# i2c_rs232_interface.net
KiCad netlist of a schematic drawn in EAGLE
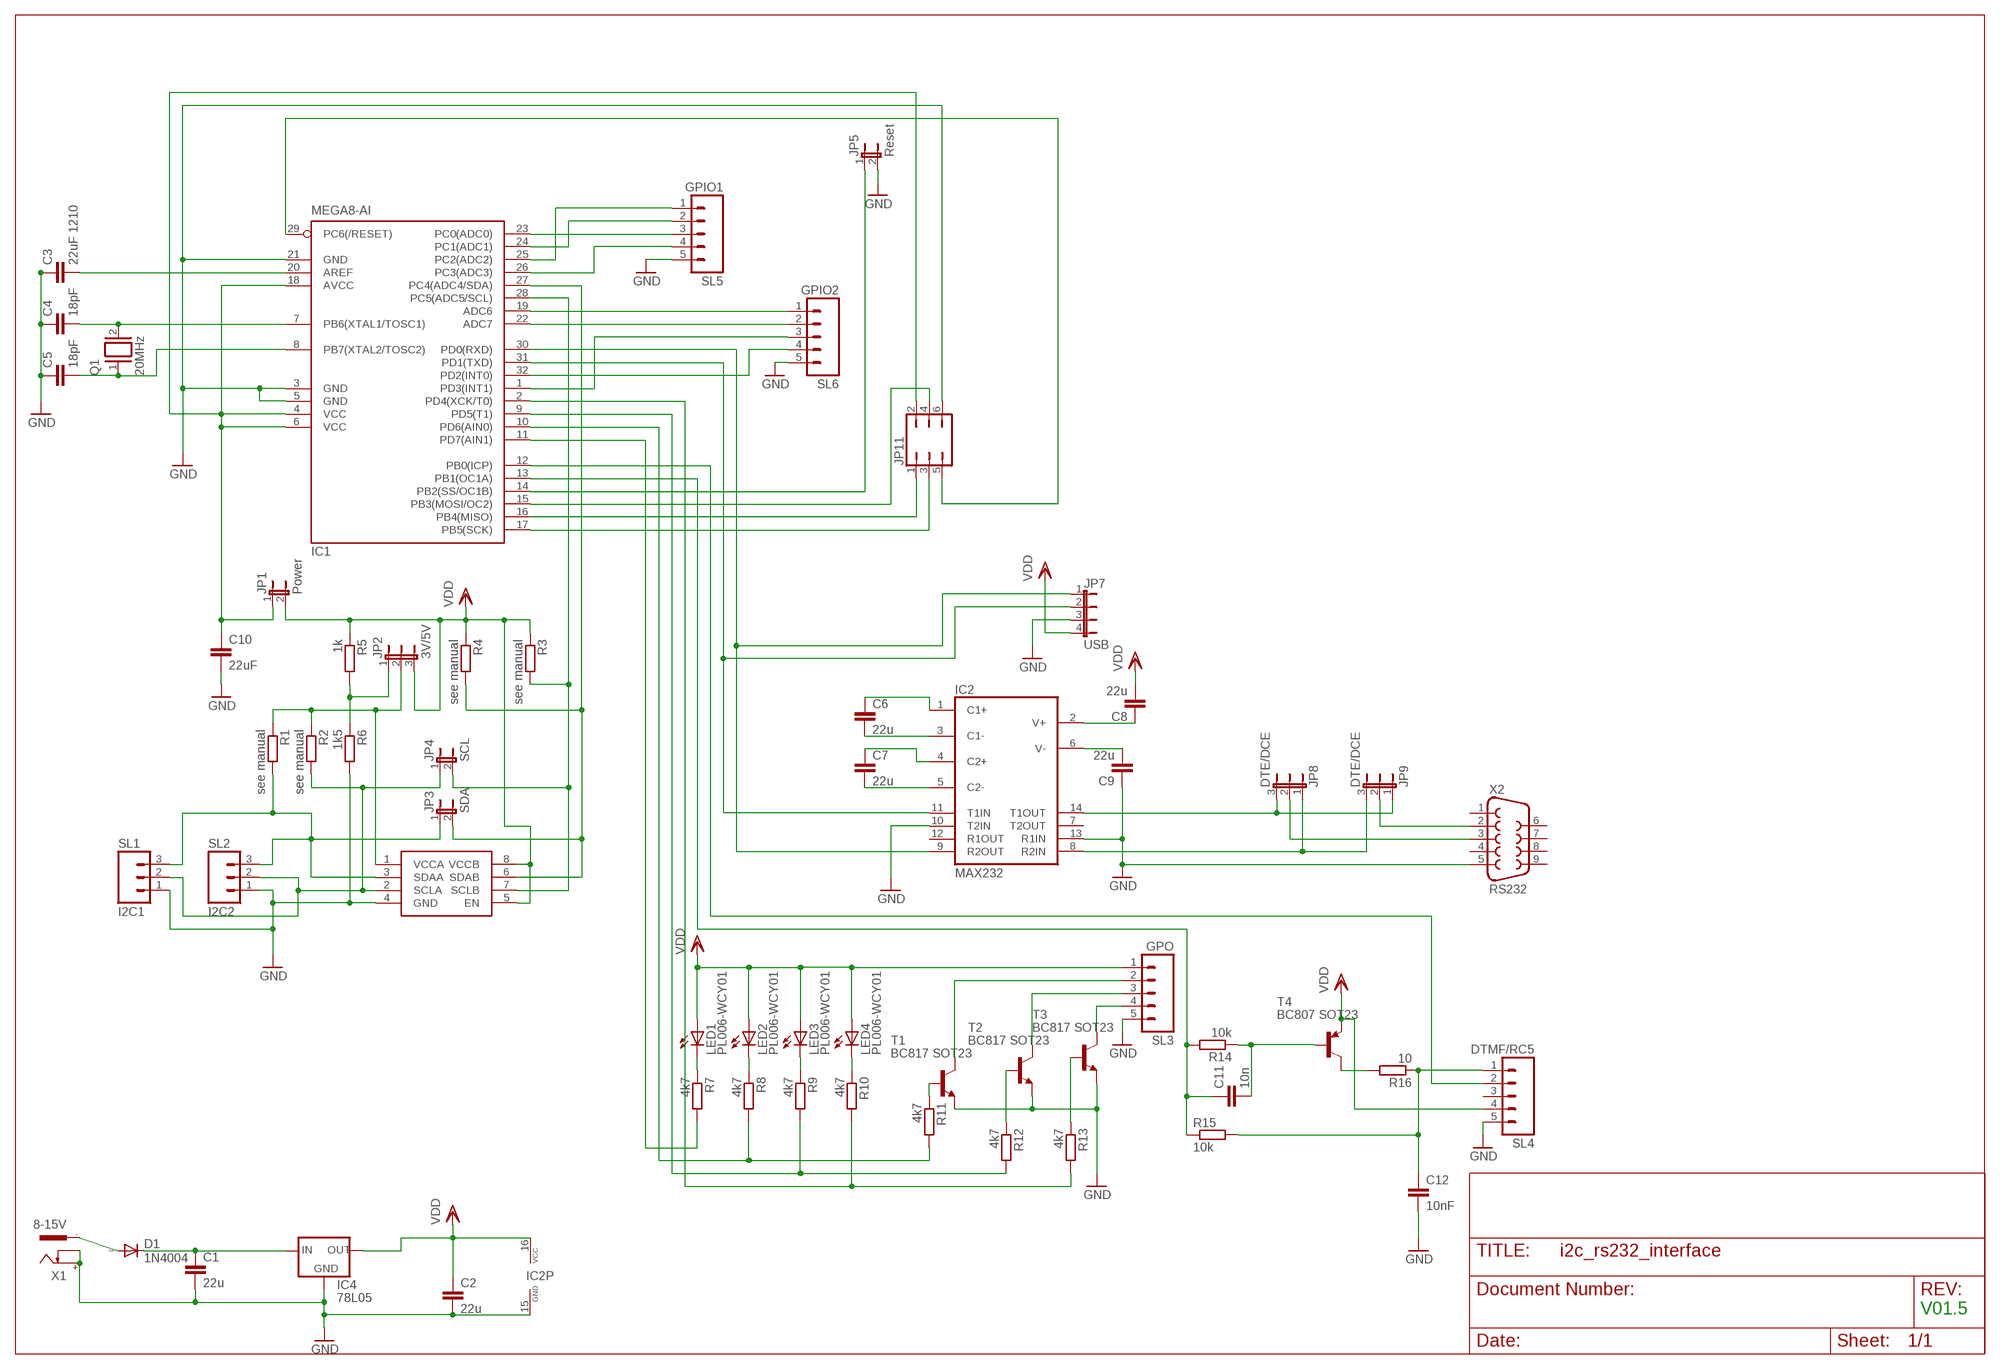
[diagram p0: schematic, sheet 1]

(export (version "E")
  (design (tool "Eeschema 10.0.6"))
  (components
    (comp (ref "C1")
      (value "22u")
      (footprint "eagle-import:C1206")
      (libsource (lib "eagle-import") (part "C-EUC1206"))
    )
    (comp (ref "C2")
      (value "22u")
      (footprint "eagle-import:C1206")
      (libsource (lib "eagle-import") (part "C-EUC1206"))
    )
    (comp (ref "C3")
      (value "22uF 1210")
      (footprint "eagle-import:C1206")
      (libsource (lib "eagle-import") (part "C-EUC1206"))
    )
    (comp (ref "C4")
      (value "18pF")
      (footprint "eagle-import:C025-025X050")
      (libsource (lib "eagle-import") (part "resistor_C-EU025-025X050"))
    )
    (comp (ref "C5")
      (value "18pF")
      (footprint "eagle-import:C025-025X050")
      (libsource (lib "eagle-import") (part "resistor_C-EU025-025X050"))
    )
    (comp (ref "C6")
      (value "22u")
      (footprint "eagle-import:C1206")
      (libsource (lib "eagle-import") (part "C-EUC1206"))
    )
    (comp (ref "C7")
      (value "22u")
      (footprint "eagle-import:C1206")
      (libsource (lib "eagle-import") (part "C-EUC1206"))
    )
    (comp (ref "C8")
      (value "22u")
      (footprint "eagle-import:C1206")
      (libsource (lib "eagle-import") (part "C-EUC1206"))
    )
    (comp (ref "C9")
      (value "22u")
      (footprint "eagle-import:C1206")
      (libsource (lib "eagle-import") (part "C-EUC1206"))
    )
    (comp (ref "C10")
      (value "22uF")
      (footprint "eagle-import:C1206")
      (libsource (lib "eagle-import") (part "C-EUC1206"))
    )
    (comp (ref "C11")
      (value "10n")
      (footprint "eagle-import:C1206")
      (libsource (lib "eagle-import") (part "resistor_C-EUC1206"))
    )
    (comp (ref "C12")
      (value "10nF")
      (footprint "eagle-import:C1206")
      (libsource (lib "eagle-import") (part "resistor_C-EUC1206"))
    )
    (comp (ref "D1")
      (value "1N4004")
      (footprint "eagle-import:DO41-10")
      (libsource (lib "eagle-import") (part "1N4004"))
    )
    (comp (ref "IC1")
      (value "MEGA8-AI")
      (footprint "eagle-import:TQFP32-08")
      (fields (field (name "MPN") "ATMEGA8-16AU"))
      (libsource (lib "eagle-import") (part "MEGA8-AI"))
    )
    (comp (ref "IC2")
      (value "MAX232")
      (footprint "eagle-import:DIL16")
      (fields (field (name "MF") "MAXIM") (field (name "MPN") "MAX232ACPE+"))
      (libsource (lib "eagle-import") (part "MAX232"))
    )
    (comp (ref "IC3")
      (value "PCA9517")
      (footprint "eagle-import:SO-08")
      (libsource (lib "eagle-import") (part "PCA9517"))
    )
    (comp (ref "IC4")
      (value "78L05")
      (footprint "eagle-import:78LXX")
      (libsource (lib "eagle-import") (part "78LXX"))
    )
    (comp (ref "JP1")
      (value "Power")
      (footprint "eagle-import:JP1")
      (libsource (lib "eagle-import") (part "JP1E"))
    )
    (comp (ref "JP2")
      (value "3V/5V")
      (footprint "eagle-import:JP2")
      (libsource (lib "eagle-import") (part "JP2E"))
    )
    (comp (ref "JP3")
      (value "SDA")
      (footprint "eagle-import:JP1")
      (libsource (lib "eagle-import") (part "JP1E"))
    )
    (comp (ref "JP4")
      (value "SCL")
      (footprint "eagle-import:JP1")
      (libsource (lib "eagle-import") (part "JP1E"))
    )
    (comp (ref "JP5")
      (value "Reset")
      (footprint "eagle-import:JP1")
      (libsource (lib "eagle-import") (part "JP1E"))
    )
    (comp (ref "JP7")
      (value "USB")
      (footprint "eagle-import:JP4")
      (libsource (lib "eagle-import") (part "JP4E"))
    )
    (comp (ref "JP8")
      (value "DTE/DCE")
      (footprint "eagle-import:JP2")
      (libsource (lib "eagle-import") (part "JP2E"))
    )
    (comp (ref "JP9")
      (value "DTE/DCE")
      (footprint "eagle-import:JP2")
      (libsource (lib "eagle-import") (part "JP2E"))
    )
    (comp (ref "JP11")
      (value "JP3Q")
      (footprint "eagle-import:JP3Q")
      (libsource (lib "eagle-import") (part "JP3Q"))
    )
    (comp (ref "LED1")
      (value "PL006-WCY01")
      (footprint "eagle-import:SOT23")
      (libsource (lib "eagle-import") (part "PL006-WCY01"))
    )
    (comp (ref "LED2")
      (value "PL006-WCY01")
      (footprint "eagle-import:SOT23")
      (libsource (lib "eagle-import") (part "PL006-WCY01"))
    )
    (comp (ref "LED3")
      (value "PL006-WCY01")
      (footprint "eagle-import:SOT23")
      (libsource (lib "eagle-import") (part "PL006-WCY01"))
    )
    (comp (ref "LED4")
      (value "PL006-WCY01")
      (footprint "eagle-import:SOT23")
      (libsource (lib "eagle-import") (part "PL006-WCY01"))
    )
    (comp (ref "Q1")
      (value "20MHz")
      (footprint "eagle-import:QS")
      (libsource (lib "eagle-import") (part "XTAL/S"))
    )
    (comp (ref "R1")
      (value "see manual")
      (footprint "eagle-import:R1206")
      (libsource (lib "eagle-import") (part "R-EU_R1206"))
    )
    (comp (ref "R2")
      (value "see manual")
      (footprint "eagle-import:R1206")
      (libsource (lib "eagle-import") (part "R-EU_R1206"))
    )
    (comp (ref "R3")
      (value "see manual")
      (footprint "eagle-import:R1206")
      (libsource (lib "eagle-import") (part "R-EU_R1206"))
    )
    (comp (ref "R4")
      (value "see manual")
      (footprint "eagle-import:R1206")
      (libsource (lib "eagle-import") (part "R-EU_R1206"))
    )
    (comp (ref "R5")
      (value "1k")
      (footprint "eagle-import:R1206")
      (libsource (lib "eagle-import") (part "R-EU_R1206"))
    )
    (comp (ref "R6")
      (value "1k5")
      (footprint "eagle-import:R1206")
      (libsource (lib "eagle-import") (part "R-EU_R1206"))
    )
    (comp (ref "R7")
      (value "4k7")
      (footprint "eagle-import:R1206")
      (libsource (lib "eagle-import") (part "R-EU_R1206"))
    )
    (comp (ref "R8")
      (value "4k7")
      (footprint "eagle-import:R1206")
      (libsource (lib "eagle-import") (part "R-EU_R1206"))
    )
    (comp (ref "R9")
      (value "4k7")
      (footprint "eagle-import:R1206")
      (libsource (lib "eagle-import") (part "R-EU_R1206"))
    )
    (comp (ref "R10")
      (value "4k7")
      (footprint "eagle-import:R1206")
      (libsource (lib "eagle-import") (part "R-EU_R1206"))
    )
    (comp (ref "R11")
      (value "4k7")
      (footprint "eagle-import:R1206")
      (libsource (lib "eagle-import") (part "R-EU_R1206"))
    )
    (comp (ref "R12")
      (value "4k7")
      (footprint "eagle-import:R1206")
      (libsource (lib "eagle-import") (part "R-EU_R1206"))
    )
    (comp (ref "R13")
      (value "4k7")
      (footprint "eagle-import:R1206")
      (libsource (lib "eagle-import") (part "R-EU_R1206"))
    )
    (comp (ref "R14")
      (value "10k")
      (footprint "eagle-import:R1206")
      (libsource (lib "eagle-import") (part "R-EU_R1206"))
    )
    (comp (ref "R15")
      (value "10k")
      (footprint "eagle-import:R1206")
      (libsource (lib "eagle-import") (part "R-EU_R1206"))
    )
    (comp (ref "R16")
      (value "10")
      (footprint "eagle-import:R1206")
      (libsource (lib "eagle-import") (part "R-EU_R1206"))
    )
    (comp (ref "SL1")
      (value "I2C1")
      (footprint "eagle-import:03P")
      (libsource (lib "eagle-import") (part "M03"))
    )
    (comp (ref "SL2")
      (value "I2C2")
      (footprint "eagle-import:03P")
      (libsource (lib "eagle-import") (part "M03"))
    )
    (comp (ref "SL3")
      (value "GPO")
      (footprint "eagle-import:05P")
      (libsource (lib "eagle-import") (part "M05"))
    )
    (comp (ref "SL4")
      (value "DTMF/RC5")
      (footprint "eagle-import:05P")
      (libsource (lib "eagle-import") (part "M05"))
    )
    (comp (ref "SL5")
      (value "GPIO1")
      (footprint "eagle-import:05P")
      (libsource (lib "eagle-import") (part "M05"))
    )
    (comp (ref "SL6")
      (value "GPIO2")
      (footprint "eagle-import:05P")
      (libsource (lib "eagle-import") (part "M05"))
    )
    (comp (ref "T1")
      (value "BC817 SOT23")
      (footprint "eagle-import:SOT23-BEC")
      (libsource (lib "eagle-import") (part "-NPN-SOT23-BECBC817"))
    )
    (comp (ref "T2")
      (value "BC817 SOT23")
      (footprint "eagle-import:SOT23-BEC")
      (libsource (lib "eagle-import") (part "-NPN-SOT23-BECBC817"))
    )
    (comp (ref "T3")
      (value "BC817 SOT23")
      (footprint "eagle-import:SOT23-BEC")
      (libsource (lib "eagle-import") (part "-NPN-SOT23-BECBC817"))
    )
    (comp (ref "T4")
      (value "BC807 SOT23")
      (footprint "eagle-import:SOT23-BEC")
      (libsource (lib "eagle-import") (part "BC807SMD-25"))
    )
    (comp (ref "X1")
      (value "8-15V")
      (footprint "eagle-import:737992-5")
      (libsource (lib "eagle-import") (part "737992-55"))
    )
    (comp (ref "X2")
      (value "RS232")
      (footprint "eagle-import:F09H")
      (libsource (lib "eagle-import") (part "F09H"))
    )
  )
  (nets
    (net (code "1") (name "GND") (class "Default")
      (node (ref "C1") (pin "2") (pinfunction "2_2") (pintype "passive"))
      (node (ref "C10") (pin "2") (pinfunction "2_2") (pintype "passive"))
      (node (ref "C12") (pin "2") (pinfunction "2_2") (pintype "passive"))
      (node (ref "C2") (pin "2") (pinfunction "2_2") (pintype "passive"))
      (node (ref "C3") (pin "1") (pinfunction "1_1") (pintype "passive"))
      (node (ref "C4") (pin "1") (pinfunction "1_1") (pintype "passive"))
      (node (ref "C5") (pin "1") (pinfunction "1_1") (pintype "passive"))
      (node (ref "C9") (pin "1") (pinfunction "1_1") (pintype "passive"))
      (node (ref "IC1") (pin "21") (pinfunction "GND_21") (pintype "power_in"))
      (node (ref "IC1") (pin "3") (pinfunction "GND_3") (pintype "power_in"))
      (node (ref "IC1") (pin "5") (pinfunction "GND_5") (pintype "power_in"))
      (node (ref "IC2") (pin "10") (pinfunction "T2IN_10") (pintype "input"))
      (node (ref "IC2") (pin "13") (pinfunction "R1IN_13") (pintype "input"))
      (node (ref "IC2") (pin "15") (pinfunction "GND_15") (pintype "power_in"))
      (node (ref "IC3") (pin "4") (pinfunction "GND_4") (pintype "bidirectional"))
      (node (ref "IC4") (pin "GND") (pinfunction "GND_GND") (pintype "input"))
      (node (ref "JP11") (pin "6") (pinfunction "6_6") (pintype "passive"))
      (node (ref "JP5") (pin "2") (pinfunction "2_2") (pintype "passive"))
      (node (ref "JP7") (pin "3") (pinfunction "3_3") (pintype "passive"))
      (node (ref "R6") (pin "2") (pinfunction "2_2") (pintype "passive"))
      (node (ref "SL1") (pin "1") (pinfunction "1_1") (pintype "passive"))
      (node (ref "SL2") (pin "1") (pinfunction "1_1") (pintype "passive"))
      (node (ref "SL3") (pin "5") (pinfunction "5_5") (pintype "passive"))
      (node (ref "SL4") (pin "5") (pinfunction "5_5") (pintype "passive"))
      (node (ref "SL5") (pin "5") (pinfunction "5_5") (pintype "passive"))
      (node (ref "SL6") (pin "5") (pinfunction "5_5") (pintype "passive"))
      (node (ref "T1") (pin "E") (pinfunction "E_E") (pintype "passive"))
      (node (ref "T2") (pin "E") (pinfunction "E_E") (pintype "passive"))
      (node (ref "T3") (pin "E") (pinfunction "E_E") (pintype "passive"))
      (node (ref "X1") (pin "+") (pinfunction "+_+") (pintype "passive"))
      (node (ref "X1") (pin "K") (pinfunction "K_K") (pintype "passive"))
      (node (ref "X2") (pin "5") (pinfunction "5_5") (pintype "passive"))
    )
    (net (code "2") (name "Net-(C1-Pad1)") (class "Default")
      (node (ref "C1") (pin "1") (pinfunction "1_1") (pintype "passive"))
      (node (ref "D1") (pin "C") (pinfunction "C_C") (pintype "passive"))
      (node (ref "IC4") (pin "IN") (pinfunction "IN_IN") (pintype "input"))
    )
    (net (code "3") (name "Net-(C11-Pad2)") (class "Default")
      (node (ref "C11") (pin "2") (pinfunction "2_2") (pintype "passive"))
      (node (ref "R14") (pin "1") (pinfunction "1_1") (pintype "passive"))
      (node (ref "T4") (pin "B") (pinfunction "B_B") (pintype "passive"))
    )
    (net (code "4") (name "Net-(C12-Pad1)") (class "Default")
      (node (ref "C12") (pin "1") (pinfunction "1_1") (pintype "passive"))
      (node (ref "R15") (pin "2") (pinfunction "2_2") (pintype "passive"))
      (node (ref "R16") (pin "1") (pinfunction "1_1") (pintype "passive"))
      (node (ref "SL4") (pin "1") (pinfunction "1_1") (pintype "passive"))
    )
    (net (code "5") (name "Net-(D1-PadA)") (class "Default")
      (node (ref "D1") (pin "A") (pinfunction "A_A") (pintype "passive"))
      (node (ref "X1") (pin "-1") (pinfunction "-1_-1") (pintype "passive"))
    )
    (net (code "6") (name "Net-(IC1-ADC6)") (class "Default")
      (node (ref "IC1") (pin "19") (pinfunction "ADC6_19") (pintype "bidirectional"))
      (node (ref "SL6") (pin "1") (pinfunction "1_1") (pintype "passive"))
    )
    (net (code "7") (name "Net-(IC1-ADC7)") (class "Default")
      (node (ref "IC1") (pin "22") (pinfunction "ADC7_22") (pintype "bidirectional"))
      (node (ref "SL6") (pin "2") (pinfunction "2_2") (pintype "passive"))
    )
    (net (code "8") (name "Net-(IC1-AREF)") (class "Default")
      (node (ref "C3") (pin "2") (pinfunction "2_2") (pintype "passive"))
      (node (ref "IC1") (pin "20") (pinfunction "AREF_20") (pintype "passive"))
    )
    (net (code "9") (name "Net-(IC1-AVCC)") (class "Default")
      (node (ref "C10") (pin "1") (pinfunction "1_1") (pintype "passive"))
      (node (ref "IC1") (pin "18") (pinfunction "AVCC_18") (pintype "power_in"))
      (node (ref "IC1") (pin "4") (pinfunction "VCC_4") (pintype "power_in"))
      (node (ref "IC1") (pin "6") (pinfunction "VCC_6") (pintype "power_in"))
      (node (ref "JP1") (pin "1") (pinfunction "1_1") (pintype "passive"))
      (node (ref "JP11") (pin "2") (pinfunction "2_2") (pintype "passive"))
    )
    (net (code "10") (name "Net-(IC1-PB0(ICP))") (class "Default")
      (node (ref "IC1") (pin "12") (pinfunction "PB0(ICP)_12") (pintype "bidirectional"))
      (node (ref "SL4") (pin "2") (pinfunction "2_2") (pintype "passive"))
    )
    (net (code "11") (name "Net-(IC1-PB1(OC1A))") (class "Default")
      (node (ref "C11") (pin "1") (pinfunction "1_1") (pintype "passive"))
      (node (ref "IC1") (pin "13") (pinfunction "PB1(OC1A)_13") (pintype "bidirectional"))
      (node (ref "R14") (pin "2") (pinfunction "2_2") (pintype "passive"))
      (node (ref "R15") (pin "1") (pinfunction "1_1") (pintype "passive"))
    )
    (net (code "12") (name "Net-(IC1-PB2(SS{slash}OC1B))") (class "Default")
      (node (ref "IC1") (pin "14") (pinfunction "PB2(SS/OC1B)_14") (pintype "bidirectional"))
      (node (ref "JP5") (pin "1") (pinfunction "1_1") (pintype "passive"))
    )
    (net (code "13") (name "Net-(IC1-PB3(MOSI{slash}OC2))") (class "Default")
      (node (ref "IC1") (pin "15") (pinfunction "PB3(MOSI/OC2)_15") (pintype "bidirectional"))
      (node (ref "JP11") (pin "4") (pinfunction "4_4") (pintype "passive"))
    )
    (net (code "14") (name "Net-(IC1-PB4(MISO))") (class "Default")
      (node (ref "IC1") (pin "16") (pinfunction "PB4(MISO)_16") (pintype "bidirectional"))
      (node (ref "JP11") (pin "1") (pinfunction "1_1") (pintype "passive"))
    )
    (net (code "15") (name "Net-(IC1-PB5(SCK))") (class "Default")
      (node (ref "IC1") (pin "17") (pinfunction "PB5(SCK)_17") (pintype "bidirectional"))
      (node (ref "JP11") (pin "3") (pinfunction "3_3") (pintype "passive"))
    )
    (net (code "16") (name "Net-(IC1-PB6(XTAL1{slash}TOSC1))") (class "Default")
      (node (ref "C4") (pin "2") (pinfunction "2_2") (pintype "passive"))
      (node (ref "IC1") (pin "7") (pinfunction "PB6(XTAL1/TOSC1)_7") (pintype "bidirectional"))
      (node (ref "Q1") (pin "2") (pinfunction "2_2") (pintype "passive"))
    )
    (net (code "17") (name "Net-(IC1-PB7(XTAL2{slash}TOSC2))") (class "Default")
      (node (ref "C5") (pin "2") (pinfunction "2_2") (pintype "passive"))
      (node (ref "IC1") (pin "8") (pinfunction "PB7(XTAL2/TOSC2)_8") (pintype "bidirectional"))
      (node (ref "Q1") (pin "1") (pinfunction "1_1") (pintype "passive"))
    )
    (net (code "18") (name "Net-(IC1-PC0(ADC0))") (class "Default")
      (node (ref "IC1") (pin "23") (pinfunction "PC0(ADC0)_23") (pintype "bidirectional"))
      (node (ref "SL5") (pin "3") (pinfunction "3_3") (pintype "passive"))
    )
    (net (code "19") (name "Net-(IC1-PC1(ADC1))") (class "Default")
      (node (ref "IC1") (pin "24") (pinfunction "PC1(ADC1)_24") (pintype "bidirectional"))
      (node (ref "SL5") (pin "2") (pinfunction "2_2") (pintype "passive"))
    )
    (net (code "20") (name "Net-(IC1-PC2(ADC2))") (class "Default")
      (node (ref "IC1") (pin "25") (pinfunction "PC2(ADC2)_25") (pintype "bidirectional"))
      (node (ref "SL5") (pin "1") (pinfunction "1_1") (pintype "passive"))
    )
    (net (code "21") (name "Net-(IC1-PC3(ADC3))") (class "Default")
      (node (ref "IC1") (pin "26") (pinfunction "PC3(ADC3)_26") (pintype "bidirectional"))
      (node (ref "SL5") (pin "4") (pinfunction "4_4") (pintype "passive"))
    )
    (net (code "22") (name "Net-(IC1-PC4(ADC4{slash}SDA))") (class "Default")
      (node (ref "IC1") (pin "27") (pinfunction "PC4(ADC4/SDA)_27") (pintype "bidirectional"))
      (node (ref "IC3") (pin "6") (pinfunction "SDAB_6") (pintype "bidirectional"))
      (node (ref "JP3") (pin "2") (pinfunction "2_2") (pintype "passive"))
      (node (ref "R4") (pin "2") (pinfunction "2_2") (pintype "passive"))
    )
    (net (code "23") (name "Net-(IC1-PC5(ADC5{slash}SCL))") (class "Default")
      (node (ref "IC1") (pin "28") (pinfunction "PC5(ADC5/SCL)_28") (pintype "bidirectional"))
      (node (ref "IC3") (pin "7") (pinfunction "SCLB_7") (pintype "bidirectional"))
      (node (ref "JP4") (pin "2") (pinfunction "2_2") (pintype "passive"))
      (node (ref "R3") (pin "2") (pinfunction "2_2") (pintype "passive"))
    )
    (net (code "24") (name "Net-(IC1-PC6({slash}RESET))") (class "Default")
      (node (ref "IC1") (pin "29") (pinfunction "PC6(/RESET)_29") (pintype "bidirectional"))
      (node (ref "JP11") (pin "5") (pinfunction "5_5") (pintype "passive"))
    )
    (net (code "25") (name "Net-(IC1-PD0(RXD))") (class "Default")
      (node (ref "IC1") (pin "30") (pinfunction "PD0(RXD)_30") (pintype "bidirectional"))
      (node (ref "IC2") (pin "9") (pinfunction "R2OUT_9") (pintype "output"))
      (node (ref "JP7") (pin "1") (pinfunction "1_1") (pintype "passive"))
    )
    (net (code "26") (name "Net-(IC1-PD1(TXD))") (class "Default")
      (node (ref "IC1") (pin "31") (pinfunction "PD1(TXD)_31") (pintype "bidirectional"))
      (node (ref "IC2") (pin "11") (pinfunction "T1IN_11") (pintype "input"))
      (node (ref "JP7") (pin "2") (pinfunction "2_2") (pintype "passive"))
    )
    (net (code "27") (name "Net-(IC1-PD2(INT0))") (class "Default")
      (node (ref "IC1") (pin "32") (pinfunction "PD2(INT0)_32") (pintype "bidirectional"))
      (node (ref "SL6") (pin "4") (pinfunction "4_4") (pintype "passive"))
    )
    (net (code "28") (name "Net-(IC1-PD3(INT1))") (class "Default")
      (node (ref "IC1") (pin "1") (pinfunction "PD3(INT1)_1") (pintype "bidirectional"))
      (node (ref "SL6") (pin "3") (pinfunction "3_3") (pintype "passive"))
    )
    (net (code "29") (name "Net-(IC1-PD4(XCK{slash}T0))") (class "Default")
      (node (ref "IC1") (pin "2") (pinfunction "PD4(XCK/T0)_2") (pintype "bidirectional"))
      (node (ref "R10") (pin "2") (pinfunction "2_2") (pintype "passive"))
      (node (ref "R13") (pin "2") (pinfunction "2_2") (pintype "passive"))
    )
    (net (code "30") (name "Net-(IC1-PD5(T1))") (class "Default")
      (node (ref "IC1") (pin "9") (pinfunction "PD5(T1)_9") (pintype "bidirectional"))
      (node (ref "R12") (pin "2") (pinfunction "2_2") (pintype "passive"))
      (node (ref "R9") (pin "2") (pinfunction "2_2") (pintype "passive"))
    )
    (net (code "31") (name "Net-(IC1-PD6(AIN0))") (class "Default")
      (node (ref "IC1") (pin "10") (pinfunction "PD6(AIN0)_10") (pintype "bidirectional"))
      (node (ref "R11") (pin "2") (pinfunction "2_2") (pintype "passive"))
      (node (ref "R8") (pin "2") (pinfunction "2_2") (pintype "passive"))
    )
    (net (code "32") (name "Net-(IC1-PD7(AIN1))") (class "Default")
      (node (ref "IC1") (pin "11") (pinfunction "PD7(AIN1)_11") (pintype "bidirectional"))
      (node (ref "R7") (pin "2") (pinfunction "2_2") (pintype "passive"))
    )
    (net (code "33") (name "Net-(IC2A-C1+)") (class "Default")
      (node (ref "C6") (pin "1") (pinfunction "1_1") (pintype "passive"))
      (node (ref "IC2") (pin "1") (pinfunction "C1+_1") (pintype "bidirectional"))
    )
    (net (code "34") (name "Net-(IC2A-C1-)") (class "Default")
      (node (ref "C6") (pin "2") (pinfunction "2_2") (pintype "passive"))
      (node (ref "IC2") (pin "3") (pinfunction "C1-_3") (pintype "bidirectional"))
    )
    (net (code "35") (name "Net-(IC2A-C2+)") (class "Default")
      (node (ref "C7") (pin "1") (pinfunction "1_1") (pintype "passive"))
      (node (ref "IC2") (pin "4") (pinfunction "C2+_4") (pintype "bidirectional"))
    )
    (net (code "36") (name "Net-(IC2A-C2-)") (class "Default")
      (node (ref "C7") (pin "2") (pinfunction "2_2") (pintype "passive"))
      (node (ref "IC2") (pin "5") (pinfunction "C2-_5") (pintype "bidirectional"))
    )
    (net (code "37") (name "Net-(IC2A-R2IN)") (class "Default")
      (node (ref "IC2") (pin "8") (pinfunction "R2IN_8") (pintype "input"))
      (node (ref "JP8") (pin "1") (pinfunction "1_1") (pintype "passive"))
      (node (ref "JP9") (pin "3") (pinfunction "3_3") (pintype "passive"))
    )
    (net (code "38") (name "Net-(IC2A-T1OUT)") (class "Default")
      (node (ref "IC2") (pin "14") (pinfunction "T1OUT_14") (pintype "output"))
      (node (ref "JP8") (pin "3") (pinfunction "3_3") (pintype "passive"))
      (node (ref "JP9") (pin "1") (pinfunction "1_1") (pintype "passive"))
    )
    (net (code "39") (name "Net-(IC2A-V+)") (class "Default")
      (node (ref "C8") (pin "1") (pinfunction "1_1") (pintype "passive"))
      (node (ref "IC2") (pin "2") (pinfunction "V+_2") (pintype "bidirectional"))
    )
    (net (code "40") (name "Net-(IC2A-V-)") (class "Default")
      (node (ref "C9") (pin "2") (pinfunction "2_2") (pintype "passive"))
      (node (ref "IC2") (pin "6") (pinfunction "V-_6") (pintype "bidirectional"))
    )
    (net (code "41") (name "Net-(IC3-SCLA)") (class "Default")
      (node (ref "IC3") (pin "2") (pinfunction "SCLA_2") (pintype "bidirectional"))
      (node (ref "JP4") (pin "1") (pinfunction "1_1") (pintype "passive"))
      (node (ref "R2") (pin "2") (pinfunction "2_2") (pintype "passive"))
      (node (ref "SL1") (pin "2") (pinfunction "2_2") (pintype "passive"))
      (node (ref "SL2") (pin "2") (pinfunction "2_2") (pintype "passive"))
    )
    (net (code "42") (name "Net-(IC3-SDAA)") (class "Default")
      (node (ref "IC3") (pin "3") (pinfunction "SDAA_3") (pintype "bidirectional"))
      (node (ref "JP3") (pin "1") (pinfunction "1_1") (pintype "passive"))
      (node (ref "R1") (pin "2") (pinfunction "2_2") (pintype "passive"))
      (node (ref "SL1") (pin "3") (pinfunction "3_3") (pintype "passive"))
      (node (ref "SL2") (pin "3") (pinfunction "3_3") (pintype "passive"))
    )
    (net (code "43") (name "Net-(IC3-VCCA)") (class "Default")
      (node (ref "IC3") (pin "1") (pinfunction "VCCA_1") (pintype "bidirectional"))
      (node (ref "JP2") (pin "2") (pinfunction "2_2") (pintype "passive"))
      (node (ref "R1") (pin "1") (pinfunction "1_1") (pintype "passive"))
      (node (ref "R2") (pin "1") (pinfunction "1_1") (pintype "passive"))
    )
    (net (code "44") (name "Net-(JP2-Pad1)") (class "Default")
      (node (ref "JP2") (pin "1") (pinfunction "1_1") (pintype "passive"))
      (node (ref "R5") (pin "2") (pinfunction "2_2") (pintype "passive"))
      (node (ref "R6") (pin "1") (pinfunction "1_1") (pintype "passive"))
    )
    (net (code "45") (name "Net-(JP8-Pad2)") (class "Default")
      (node (ref "JP8") (pin "2") (pinfunction "2_2") (pintype "passive"))
      (node (ref "X2") (pin "3") (pinfunction "3_3") (pintype "passive"))
    )
    (net (code "46") (name "Net-(JP9-Pad2)") (class "Default")
      (node (ref "JP9") (pin "2") (pinfunction "2_2") (pintype "passive"))
      (node (ref "X2") (pin "2") (pinfunction "2_2") (pintype "passive"))
    )
    (net (code "47") (name "Net-(LED1-C)") (class "Default")
      (node (ref "LED1") (pin "3") (pinfunction "C_3") (pintype "passive"))
      (node (ref "R7") (pin "1") (pinfunction "1_1") (pintype "passive"))
    )
    (net (code "48") (name "Net-(LED2-C)") (class "Default")
      (node (ref "LED2") (pin "3") (pinfunction "C_3") (pintype "passive"))
      (node (ref "R8") (pin "1") (pinfunction "1_1") (pintype "passive"))
    )
    (net (code "49") (name "Net-(LED3-C)") (class "Default")
      (node (ref "LED3") (pin "3") (pinfunction "C_3") (pintype "passive"))
      (node (ref "R9") (pin "1") (pinfunction "1_1") (pintype "passive"))
    )
    (net (code "50") (name "Net-(LED4-C)") (class "Default")
      (node (ref "LED4") (pin "3") (pinfunction "C_3") (pintype "passive"))
      (node (ref "R10") (pin "1") (pinfunction "1_1") (pintype "passive"))
    )
    (net (code "51") (name "Net-(R11-Pad1)") (class "Default")
      (node (ref "R11") (pin "1") (pinfunction "1_1") (pintype "passive"))
      (node (ref "T1") (pin "B") (pinfunction "B_B") (pintype "passive"))
    )
    (net (code "52") (name "Net-(R12-Pad1)") (class "Default")
      (node (ref "R12") (pin "1") (pinfunction "1_1") (pintype "passive"))
      (node (ref "T2") (pin "B") (pinfunction "B_B") (pintype "passive"))
    )
    (net (code "53") (name "Net-(R13-Pad1)") (class "Default")
      (node (ref "R13") (pin "1") (pinfunction "1_1") (pintype "passive"))
      (node (ref "T3") (pin "B") (pinfunction "B_B") (pintype "passive"))
    )
    (net (code "54") (name "Net-(R16-Pad2)") (class "Default")
      (node (ref "R16") (pin "2") (pinfunction "2_2") (pintype "passive"))
      (node (ref "T4") (pin "C") (pinfunction "C_C") (pintype "passive"))
    )
    (net (code "55") (name "Net-(SL3-Pad2)") (class "Default")
      (node (ref "SL3") (pin "2") (pinfunction "2_2") (pintype "passive"))
      (node (ref "T1") (pin "C") (pinfunction "C_C") (pintype "passive"))
    )
    (net (code "56") (name "Net-(SL3-Pad3)") (class "Default")
      (node (ref "SL3") (pin "3") (pinfunction "3_3") (pintype "passive"))
      (node (ref "T2") (pin "C") (pinfunction "C_C") (pintype "passive"))
    )
    (net (code "57") (name "Net-(SL3-Pad4)") (class "Default")
      (node (ref "SL3") (pin "4") (pinfunction "4_4") (pintype "passive"))
      (node (ref "T3") (pin "C") (pinfunction "C_C") (pintype "passive"))
    )
    (net (code "58") (name "VDD") (class "Default")
      (node (ref "C2") (pin "1") (pinfunction "1_1") (pintype "passive"))
      (node (ref "C8") (pin "2") (pinfunction "2_2") (pintype "passive"))
      (node (ref "IC2") (pin "16") (pinfunction "VCC_16") (pintype "power_in"))
      (node (ref "IC3") (pin "5") (pinfunction "EN_5") (pintype "bidirectional"))
      (node (ref "IC3") (pin "8") (pinfunction "VCCB_8") (pintype "bidirectional"))
      (node (ref "IC4") (pin "OUT") (pinfunction "OUT_OUT") (pintype "passive"))
      (node (ref "JP1") (pin "2") (pinfunction "2_2") (pintype "passive"))
      (node (ref "JP2") (pin "3") (pinfunction "3_3") (pintype "passive"))
      (node (ref "JP7") (pin "4") (pinfunction "4_4") (pintype "passive"))
      (node (ref "LED1") (pin "1") (pinfunction "A_1") (pintype "passive"))
      (node (ref "LED2") (pin "1") (pinfunction "A_1") (pintype "passive"))
      (node (ref "LED3") (pin "1") (pinfunction "A_1") (pintype "passive"))
      (node (ref "LED4") (pin "1") (pinfunction "A_1") (pintype "passive"))
      (node (ref "R3") (pin "1") (pinfunction "1_1") (pintype "passive"))
      (node (ref "R4") (pin "1") (pinfunction "1_1") (pintype "passive"))
      (node (ref "R5") (pin "1") (pinfunction "1_1") (pintype "passive"))
      (node (ref "SL3") (pin "1") (pinfunction "1_1") (pintype "passive"))
      (node (ref "SL4") (pin "4") (pinfunction "4_4") (pintype "passive"))
      (node (ref "T4") (pin "E") (pinfunction "E_E") (pintype "passive"))
    )
    (net (code "59") (name "unconnected-(IC2A-R1OUT-Pad12)") (class "Default")
      (node (ref "IC2") (pin "12") (pinfunction "R1OUT_12") (pintype "output"))
    )
    (net (code "60") (name "unconnected-(IC2A-T2OUT-Pad7)") (class "Default")
      (node (ref "IC2") (pin "7") (pinfunction "T2OUT_7") (pintype "output"))
    )
    (net (code "61") (name "unconnected-(SL4-Pad3)") (class "Default")
      (node (ref "SL4") (pin "3") (pinfunction "3_3") (pintype "passive"))
    )
    (net (code "62") (name "unconnected-(X1-Pad-2)") (class "Default")
      (node (ref "X1") (pin "-2") (pinfunction "-2_-2") (pintype "passive"))
    )
    (net (code "63") (name "unconnected-(X2-Pad1)") (class "Default")
      (node (ref "X2") (pin "1") (pinfunction "1_1") (pintype "passive"))
    )
    (net (code "64") (name "unconnected-(X2-Pad4)") (class "Default")
      (node (ref "X2") (pin "4") (pinfunction "4_4") (pintype "passive"))
    )
    (net (code "65") (name "unconnected-(X2-Pad6)") (class "Default")
      (node (ref "X2") (pin "6") (pinfunction "6_6") (pintype "passive"))
    )
    (net (code "66") (name "unconnected-(X2-Pad7)") (class "Default")
      (node (ref "X2") (pin "7") (pinfunction "7_7") (pintype "passive"))
    )
    (net (code "67") (name "unconnected-(X2-Pad8)") (class "Default")
      (node (ref "X2") (pin "8") (pinfunction "8_8") (pintype "passive"))
    )
    (net (code "68") (name "unconnected-(X2-Pad9)") (class "Default")
      (node (ref "X2") (pin "9") (pinfunction "9_9") (pintype "passive"))
    )
  )
)
